# cny70_array.net
KiCad netlist of a schematic drawn in EAGLE
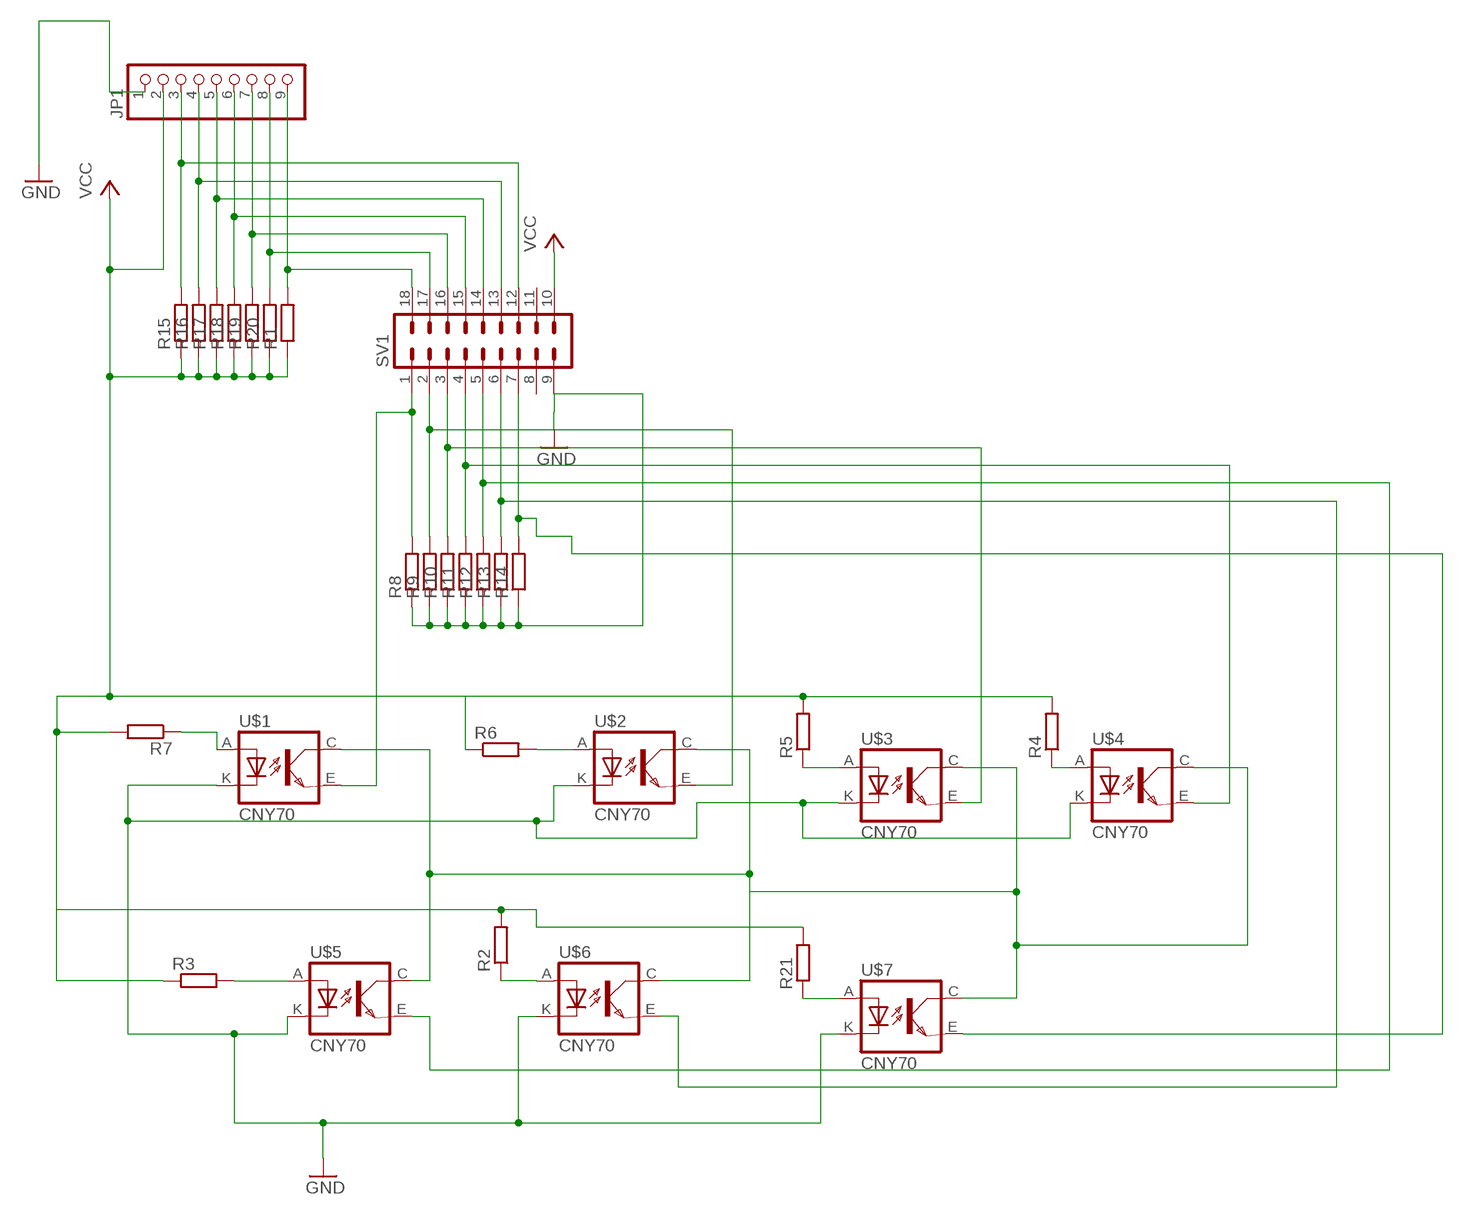
[diagram p0: schematic, sheet 1]

(export (version "E")
  (design (tool "Eeschema 10.0.6"))
  (components
    (comp (ref "JP1")
      (value "PINHD-1X9")
      (footprint "eagle-import:1X09")
      (libsource (lib "eagle-import") (part "PINHD-1X9"))
    )
    (comp (ref "R1")
      (value "R-EU_0204/5")
      (footprint "eagle-import:0204_5")
      (libsource (lib "eagle-import") (part "R-EU_0204/5"))
    )
    (comp (ref "R2")
      (value "R-EU_0204/5")
      (footprint "eagle-import:0204_5")
      (libsource (lib "eagle-import") (part "R-EU_0204/5"))
    )
    (comp (ref "R3")
      (value "R-EU_0204/5")
      (footprint "eagle-import:0204_5")
      (libsource (lib "eagle-import") (part "R-EU_0204/5"))
    )
    (comp (ref "R4")
      (value "R-EU_0204/5")
      (footprint "eagle-import:0204_5")
      (libsource (lib "eagle-import") (part "R-EU_0204/5"))
    )
    (comp (ref "R5")
      (value "R-EU_0204/5")
      (footprint "eagle-import:0204_5")
      (libsource (lib "eagle-import") (part "R-EU_0204/5"))
    )
    (comp (ref "R6")
      (value "R-EU_0204/5")
      (footprint "eagle-import:0204_5")
      (libsource (lib "eagle-import") (part "R-EU_0204/5"))
    )
    (comp (ref "R7")
      (value "R-EU_0204/5")
      (footprint "eagle-import:0204_5")
      (libsource (lib "eagle-import") (part "R-EU_0204/5"))
    )
    (comp (ref "R8")
      (value "R-EU_0204/5")
      (footprint "eagle-import:0204_5")
      (libsource (lib "eagle-import") (part "R-EU_0204/5"))
    )
    (comp (ref "R9")
      (value "R-EU_0204/5")
      (footprint "eagle-import:0204_5")
      (libsource (lib "eagle-import") (part "R-EU_0204/5"))
    )
    (comp (ref "R10")
      (value "R-EU_0204/5")
      (footprint "eagle-import:0204_5")
      (libsource (lib "eagle-import") (part "R-EU_0204/5"))
    )
    (comp (ref "R11")
      (value "R-EU_0204/5")
      (footprint "eagle-import:0204_5")
      (libsource (lib "eagle-import") (part "R-EU_0204/5"))
    )
    (comp (ref "R12")
      (value "R-EU_0204/5")
      (footprint "eagle-import:0204_5")
      (libsource (lib "eagle-import") (part "R-EU_0204/5"))
    )
    (comp (ref "R13")
      (value "R-EU_0204/5")
      (footprint "eagle-import:0204_5")
      (libsource (lib "eagle-import") (part "R-EU_0204/5"))
    )
    (comp (ref "R14")
      (value "R-EU_0204/5")
      (footprint "eagle-import:0204_5")
      (libsource (lib "eagle-import") (part "R-EU_0204/5"))
    )
    (comp (ref "R15")
      (value "R-EU_0204/5")
      (footprint "eagle-import:0204_5")
      (libsource (lib "eagle-import") (part "R-EU_0204/5"))
    )
    (comp (ref "R16")
      (value "R-EU_0204/5")
      (footprint "eagle-import:0204_5")
      (libsource (lib "eagle-import") (part "R-EU_0204/5"))
    )
    (comp (ref "R17")
      (value "R-EU_0204/5")
      (footprint "eagle-import:0204_5")
      (libsource (lib "eagle-import") (part "R-EU_0204/5"))
    )
    (comp (ref "R18")
      (value "R-EU_0204/5")
      (footprint "eagle-import:0204_5")
      (libsource (lib "eagle-import") (part "R-EU_0204/5"))
    )
    (comp (ref "R19")
      (value "R-EU_0204/5")
      (footprint "eagle-import:0204_5")
      (libsource (lib "eagle-import") (part "R-EU_0204/5"))
    )
    (comp (ref "R20")
      (value "R-EU_0204/5")
      (footprint "eagle-import:0204_5")
      (libsource (lib "eagle-import") (part "R-EU_0204/5"))
    )
    (comp (ref "R21")
      (value "R-EU_0204/5")
      (footprint "eagle-import:0204_5")
      (libsource (lib "eagle-import") (part "R-EU_0204/5"))
    )
    (comp (ref "SV1")
      (value "IC18PL")
      (footprint "eagle-import:IC18PL")
      (libsource (lib "eagle-import") (part "IC18PL"))
    )
    (comp (ref "U$1")
      (value "CNY70")
      (footprint "eagle-import:4")
      (libsource (lib "eagle-import") (part "CNY70"))
    )
    (comp (ref "U$2")
      (value "CNY70")
      (footprint "eagle-import:4")
      (libsource (lib "eagle-import") (part "CNY70"))
    )
    (comp (ref "U$3")
      (value "CNY70")
      (footprint "eagle-import:4")
      (libsource (lib "eagle-import") (part "CNY70"))
    )
    (comp (ref "U$4")
      (value "CNY70")
      (footprint "eagle-import:4")
      (libsource (lib "eagle-import") (part "CNY70"))
    )
    (comp (ref "U$5")
      (value "CNY70")
      (footprint "eagle-import:4")
      (libsource (lib "eagle-import") (part "CNY70"))
    )
    (comp (ref "U$6")
      (value "CNY70")
      (footprint "eagle-import:4")
      (libsource (lib "eagle-import") (part "CNY70"))
    )
    (comp (ref "U$7")
      (value "CNY70")
      (footprint "eagle-import:4")
      (libsource (lib "eagle-import") (part "CNY70"))
    )
  )
  (nets
    (net (code "1") (name "GND") (class "Default")
      (node (ref "JP1") (pin "1") (pinfunction "1_1") (pintype "passive"))
      (node (ref "R10") (pin "1") (pinfunction "1_1") (pintype "passive"))
      (node (ref "R11") (pin "1") (pinfunction "1_1") (pintype "passive"))
      (node (ref "R12") (pin "1") (pinfunction "1_1") (pintype "passive"))
      (node (ref "R13") (pin "1") (pinfunction "1_1") (pintype "passive"))
      (node (ref "R14") (pin "1") (pinfunction "1_1") (pintype "passive"))
      (node (ref "R8") (pin "1") (pinfunction "1_1") (pintype "passive"))
      (node (ref "R9") (pin "1") (pinfunction "1_1") (pintype "passive"))
      (node (ref "SV1") (pin "9") (pinfunction "9_9") (pintype "passive"))
      (node (ref "U$1") (pin "K") (pinfunction "C_K") (pintype "passive"))
      (node (ref "U$2") (pin "K") (pinfunction "C_K") (pintype "passive"))
      (node (ref "U$3") (pin "K") (pinfunction "C_K") (pintype "passive"))
      (node (ref "U$4") (pin "K") (pinfunction "C_K") (pintype "passive"))
      (node (ref "U$5") (pin "K") (pinfunction "C_K") (pintype "passive"))
      (node (ref "U$6") (pin "K") (pinfunction "C_K") (pintype "passive"))
      (node (ref "U$7") (pin "K") (pinfunction "C_K") (pintype "passive"))
    )
    (net (code "2") (name "Net-(JP1-Pad3)") (class "Default")
      (node (ref "JP1") (pin "3") (pinfunction "3_3") (pintype "passive"))
      (node (ref "R15") (pin "2") (pinfunction "2_2") (pintype "passive"))
      (node (ref "SV1") (pin "12") (pinfunction "12_12") (pintype "passive"))
    )
    (net (code "3") (name "Net-(JP1-Pad4)") (class "Default")
      (node (ref "JP1") (pin "4") (pinfunction "4_4") (pintype "passive"))
      (node (ref "R16") (pin "2") (pinfunction "2_2") (pintype "passive"))
      (node (ref "SV1") (pin "13") (pinfunction "13_13") (pintype "passive"))
    )
    (net (code "4") (name "Net-(JP1-Pad5)") (class "Default")
      (node (ref "JP1") (pin "5") (pinfunction "5_5") (pintype "passive"))
      (node (ref "R17") (pin "2") (pinfunction "2_2") (pintype "passive"))
      (node (ref "SV1") (pin "14") (pinfunction "14_14") (pintype "passive"))
    )
    (net (code "5") (name "Net-(JP1-Pad6)") (class "Default")
      (node (ref "JP1") (pin "6") (pinfunction "6_6") (pintype "passive"))
      (node (ref "R18") (pin "2") (pinfunction "2_2") (pintype "passive"))
      (node (ref "SV1") (pin "15") (pinfunction "15_15") (pintype "passive"))
    )
    (net (code "6") (name "Net-(JP1-Pad7)") (class "Default")
      (node (ref "JP1") (pin "7") (pinfunction "7_7") (pintype "passive"))
      (node (ref "R19") (pin "2") (pinfunction "2_2") (pintype "passive"))
      (node (ref "SV1") (pin "16") (pinfunction "16_16") (pintype "passive"))
    )
    (net (code "7") (name "Net-(JP1-Pad8)") (class "Default")
      (node (ref "JP1") (pin "8") (pinfunction "8_8") (pintype "passive"))
      (node (ref "R20") (pin "2") (pinfunction "2_2") (pintype "passive"))
      (node (ref "SV1") (pin "17") (pinfunction "17_17") (pintype "passive"))
    )
    (net (code "8") (name "Net-(JP1-Pad9)") (class "Default")
      (node (ref "JP1") (pin "9") (pinfunction "9_9") (pintype "passive"))
      (node (ref "R1") (pin "2") (pinfunction "2_2") (pintype "passive"))
      (node (ref "SV1") (pin "18") (pinfunction "18_18") (pintype "passive"))
    )
    (net (code "9") (name "Net-(R2-Pad1)") (class "Default")
      (node (ref "R2") (pin "1") (pinfunction "1_1") (pintype "passive"))
      (node (ref "U$6") (pin "A") (pinfunction "A_A") (pintype "passive"))
    )
    (net (code "10") (name "Net-(R3-Pad2)") (class "Default")
      (node (ref "R3") (pin "2") (pinfunction "2_2") (pintype "passive"))
      (node (ref "U$5") (pin "A") (pinfunction "A_A") (pintype "passive"))
    )
    (net (code "11") (name "Net-(R4-Pad1)") (class "Default")
      (node (ref "R4") (pin "1") (pinfunction "1_1") (pintype "passive"))
      (node (ref "U$4") (pin "A") (pinfunction "A_A") (pintype "passive"))
    )
    (net (code "12") (name "Net-(R5-Pad1)") (class "Default")
      (node (ref "R5") (pin "1") (pinfunction "1_1") (pintype "passive"))
      (node (ref "U$3") (pin "A") (pinfunction "A_A") (pintype "passive"))
    )
    (net (code "13") (name "Net-(R6-Pad2)") (class "Default")
      (node (ref "R6") (pin "2") (pinfunction "2_2") (pintype "passive"))
      (node (ref "U$2") (pin "A") (pinfunction "A_A") (pintype "passive"))
    )
    (net (code "14") (name "Net-(R7-Pad1)") (class "Default")
      (node (ref "R7") (pin "1") (pinfunction "1_1") (pintype "passive"))
      (node (ref "U$1") (pin "A") (pinfunction "A_A") (pintype "passive"))
    )
    (net (code "15") (name "Net-(R21-Pad1)") (class "Default")
      (node (ref "R21") (pin "1") (pinfunction "1_1") (pintype "passive"))
      (node (ref "U$7") (pin "A") (pinfunction "A_A") (pintype "passive"))
    )
    (net (code "16") (name "Net-(U$1-COL)") (class "Default")
      (node (ref "U$1") (pin "C") (pinfunction "COL_C") (pintype "passive"))
      (node (ref "U$2") (pin "C") (pinfunction "COL_C") (pintype "passive"))
      (node (ref "U$3") (pin "C") (pinfunction "COL_C") (pintype "passive"))
      (node (ref "U$4") (pin "C") (pinfunction "COL_C") (pintype "passive"))
      (node (ref "U$5") (pin "C") (pinfunction "COL_C") (pintype "passive"))
      (node (ref "U$6") (pin "C") (pinfunction "COL_C") (pintype "passive"))
      (node (ref "U$7") (pin "C") (pinfunction "COL_C") (pintype "passive"))
    )
    (net (code "17") (name "Net-(U$1-EMI)") (class "Default")
      (node (ref "R8") (pin "2") (pinfunction "2_2") (pintype "passive"))
      (node (ref "SV1") (pin "1") (pinfunction "1_1") (pintype "passive"))
      (node (ref "U$1") (pin "E") (pinfunction "EMI_E") (pintype "passive"))
    )
    (net (code "18") (name "Net-(U$2-EMI)") (class "Default")
      (node (ref "R9") (pin "2") (pinfunction "2_2") (pintype "passive"))
      (node (ref "SV1") (pin "2") (pinfunction "2_2") (pintype "passive"))
      (node (ref "U$2") (pin "E") (pinfunction "EMI_E") (pintype "passive"))
    )
    (net (code "19") (name "Net-(U$3-EMI)") (class "Default")
      (node (ref "R10") (pin "2") (pinfunction "2_2") (pintype "passive"))
      (node (ref "SV1") (pin "3") (pinfunction "3_3") (pintype "passive"))
      (node (ref "U$3") (pin "E") (pinfunction "EMI_E") (pintype "passive"))
    )
    (net (code "20") (name "Net-(U$4-EMI)") (class "Default")
      (node (ref "R11") (pin "2") (pinfunction "2_2") (pintype "passive"))
      (node (ref "SV1") (pin "4") (pinfunction "4_4") (pintype "passive"))
      (node (ref "U$4") (pin "E") (pinfunction "EMI_E") (pintype "passive"))
    )
    (net (code "21") (name "Net-(U$5-EMI)") (class "Default")
      (node (ref "R12") (pin "2") (pinfunction "2_2") (pintype "passive"))
      (node (ref "SV1") (pin "5") (pinfunction "5_5") (pintype "passive"))
      (node (ref "U$5") (pin "E") (pinfunction "EMI_E") (pintype "passive"))
    )
    (net (code "22") (name "Net-(U$6-EMI)") (class "Default")
      (node (ref "R13") (pin "2") (pinfunction "2_2") (pintype "passive"))
      (node (ref "SV1") (pin "6") (pinfunction "6_6") (pintype "passive"))
      (node (ref "U$6") (pin "E") (pinfunction "EMI_E") (pintype "passive"))
    )
    (net (code "23") (name "Net-(U$7-EMI)") (class "Default")
      (node (ref "R14") (pin "2") (pinfunction "2_2") (pintype "passive"))
      (node (ref "SV1") (pin "7") (pinfunction "7_7") (pintype "passive"))
      (node (ref "U$7") (pin "E") (pinfunction "EMI_E") (pintype "passive"))
    )
    (net (code "24") (name "VCC") (class "Default")
      (node (ref "JP1") (pin "2") (pinfunction "2_2") (pintype "passive"))
      (node (ref "R1") (pin "1") (pinfunction "1_1") (pintype "passive"))
      (node (ref "R15") (pin "1") (pinfunction "1_1") (pintype "passive"))
      (node (ref "R16") (pin "1") (pinfunction "1_1") (pintype "passive"))
      (node (ref "R17") (pin "1") (pinfunction "1_1") (pintype "passive"))
      (node (ref "R18") (pin "1") (pinfunction "1_1") (pintype "passive"))
      (node (ref "R19") (pin "1") (pinfunction "1_1") (pintype "passive"))
      (node (ref "R2") (pin "2") (pinfunction "2_2") (pintype "passive"))
      (node (ref "R20") (pin "1") (pinfunction "1_1") (pintype "passive"))
      (node (ref "R21") (pin "2") (pinfunction "2_2") (pintype "passive"))
      (node (ref "R3") (pin "1") (pinfunction "1_1") (pintype "passive"))
      (node (ref "R4") (pin "2") (pinfunction "2_2") (pintype "passive"))
      (node (ref "R5") (pin "2") (pinfunction "2_2") (pintype "passive"))
      (node (ref "R6") (pin "1") (pinfunction "1_1") (pintype "passive"))
      (node (ref "R7") (pin "2") (pinfunction "2_2") (pintype "passive"))
      (node (ref "SV1") (pin "10") (pinfunction "10_10") (pintype "passive"))
    )
    (net (code "25") (name "unconnected-(SV1-Pad8)") (class "Default")
      (node (ref "SV1") (pin "8") (pinfunction "8_8") (pintype "passive"))
    )
    (net (code "26") (name "unconnected-(SV1-Pad11)") (class "Default")
      (node (ref "SV1") (pin "11") (pinfunction "11_11") (pintype "passive"))
    )
  )
)
